# 06_KEY.net
KiCad netlist of a schematic drawn in Altium Designer
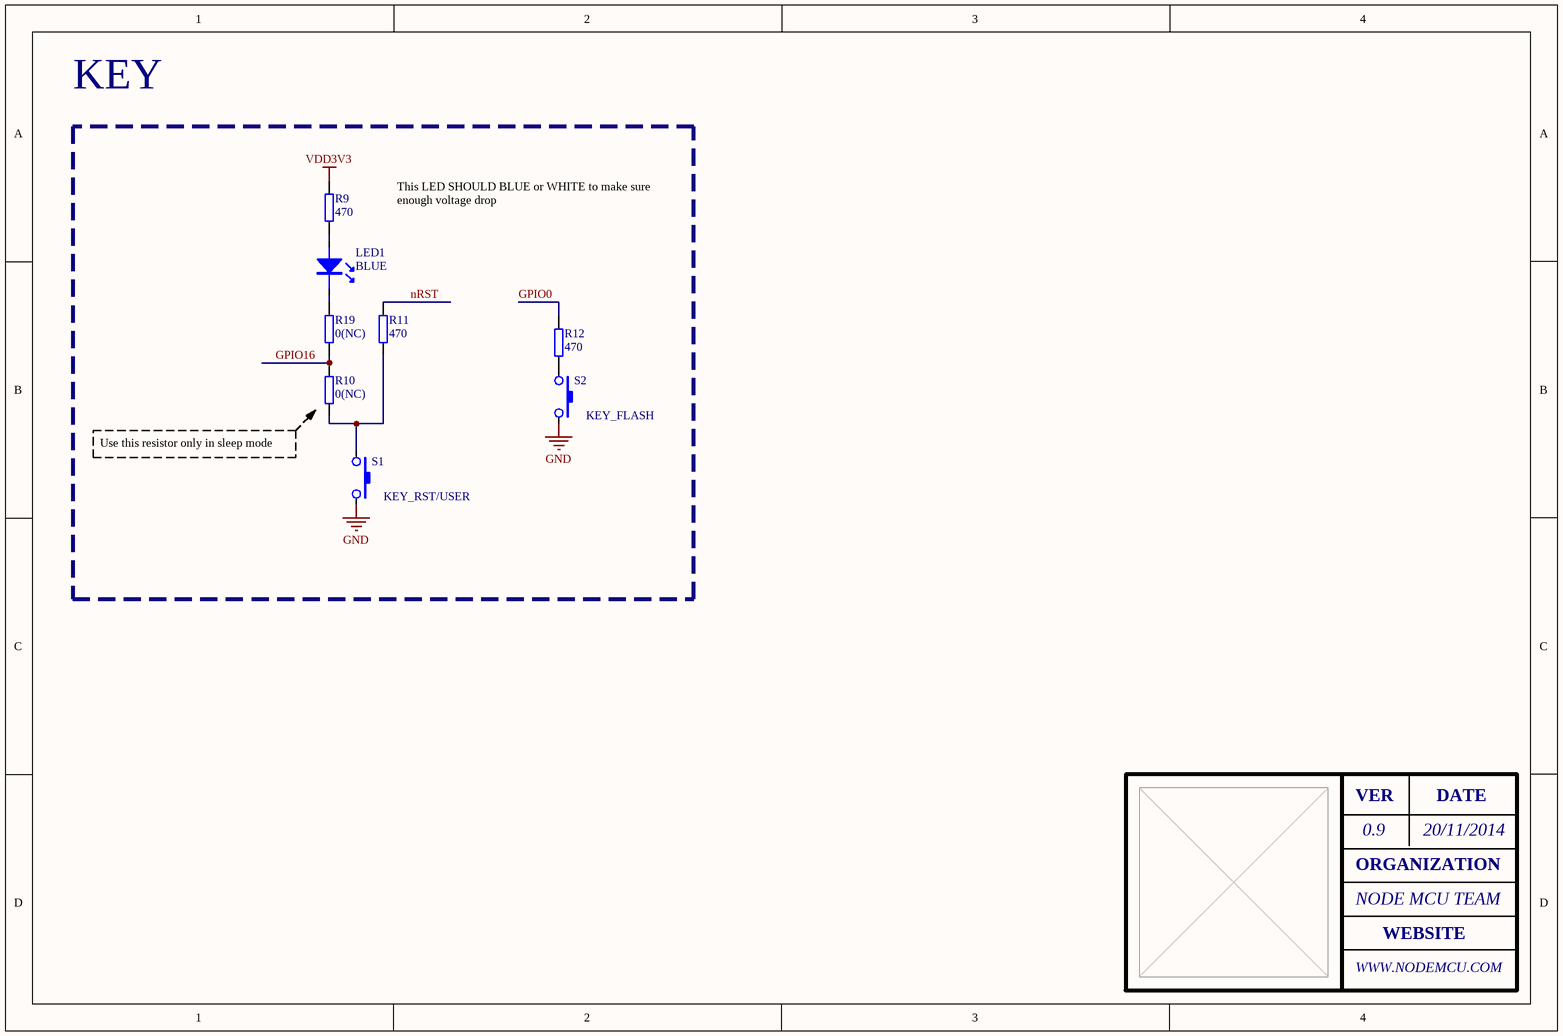
[diagram p0: 06_KEY.SchDoc]

(export (version "E")
  (design (tool "Eeschema 10.0.6"))
  (components
    (comp (ref "LED1")
      (value "BLUE")
      (footprint "SMT_LED_0603")
      (description "SMT LED")
      (libsource (lib "Vowstar_Basic_Device") (part "SMT_LED_0603"))
    )
    (comp (ref "R9")
      (value "470")
      (footprint "SMT_R_0402")
      (description "Surface mount resistor 0402")
      (libsource (lib "Vowstar_Basic_Device") (part "SMT_R_0402"))
    )
    (comp (ref "R10")
      (value "0(NC)")
      (footprint "SMT_R_0402")
      (description "Surface mount resistor 0402")
      (libsource (lib "Vowstar_Basic_Device") (part "SMT_R_0402"))
    )
    (comp (ref "R11")
      (value "470")
      (footprint "SMT_R_0402")
      (description "Surface mount resistor 0402")
      (libsource (lib "Vowstar_Basic_Device") (part "SMT_R_0402"))
    )
    (comp (ref "R12")
      (value "470")
      (footprint "SMT_R_0402")
      (description "Surface mount resistor 0402")
      (libsource (lib "Vowstar_Basic_Device") (part "SMT_R_0402"))
    )
    (comp (ref "R19")
      (value "0(NC)")
      (footprint "SMT_R_0402")
      (description "Surface mount resistor 0402")
      (libsource (lib "Vowstar_Basic_Device") (part "SMT_R_0402"))
    )
    (comp (ref "S1")
      (value "KEY_RST/USER")
      (footprint "SMT_SW_PTS_820")
      (description "SMT Tactile ‎Switch PTS 820 Series")
      (libsource (lib "Vowstar_Switch") (part "SMT_SW_PTS_820"))
    )
    (comp (ref "S2")
      (value "KEY_FLASH")
      (footprint "SMT_SW_PTS_820")
      (description "SMT Tactile ‎Switch PTS 820 Series")
      (libsource (lib "Vowstar_Switch") (part "SMT_SW_PTS_820"))
    )
  )
  (nets
    (net (code "1") (name "/GPIO0") (class "Default")
      (node (ref "R12") (pin "2") (pinfunction "2_2") (pintype "passive"))
    )
    (net (code "2") (name "/GPIO16") (class "Default")
      (node (ref "R10") (pin "2") (pinfunction "2_2") (pintype "passive"))
      (node (ref "R19") (pin "1") (pinfunction "1_1") (pintype "passive"))
    )
    (net (code "3") (name "/nRST") (class "Default")
      (node (ref "R11") (pin "2") (pinfunction "2_2") (pintype "passive"))
    )
    (net (code "4") (name "GND") (class "Default")
      (node (ref "S1") (pin "2") (pinfunction "2_2") (pintype "passive"))
      (node (ref "S2") (pin "2") (pinfunction "2_2") (pintype "passive"))
    )
    (net (code "5") (name "Net-(LED1-A)") (class "Default")
      (node (ref "LED1") (pin "1") (pinfunction "A_1") (pintype "passive"))
      (node (ref "R9") (pin "1") (pinfunction "1_1") (pintype "passive"))
    )
    (net (code "6") (name "Net-(LED1-K)") (class "Default")
      (node (ref "LED1") (pin "2") (pinfunction "K_2") (pintype "passive"))
      (node (ref "R19") (pin "2") (pinfunction "2_2") (pintype "passive"))
    )
    (net (code "7") (name "Net-(R10-Pad1)") (class "Default")
      (node (ref "R10") (pin "1") (pinfunction "1_1") (pintype "passive"))
      (node (ref "R11") (pin "1") (pinfunction "1_1") (pintype "passive"))
      (node (ref "S1") (pin "1") (pinfunction "1_1") (pintype "passive"))
    )
    (net (code "8") (name "Net-(R12-Pad1)") (class "Default")
      (node (ref "R12") (pin "1") (pinfunction "1_1") (pintype "passive"))
      (node (ref "S2") (pin "1") (pinfunction "1_1") (pintype "passive"))
    )
    (net (code "9") (name "VDD3V3") (class "Default")
      (node (ref "R9") (pin "2") (pinfunction "2_2") (pintype "passive"))
    )
  )
)
